# 3_-MCU_MAIN.net
KiCad netlist of a schematic drawn in Altium Designer
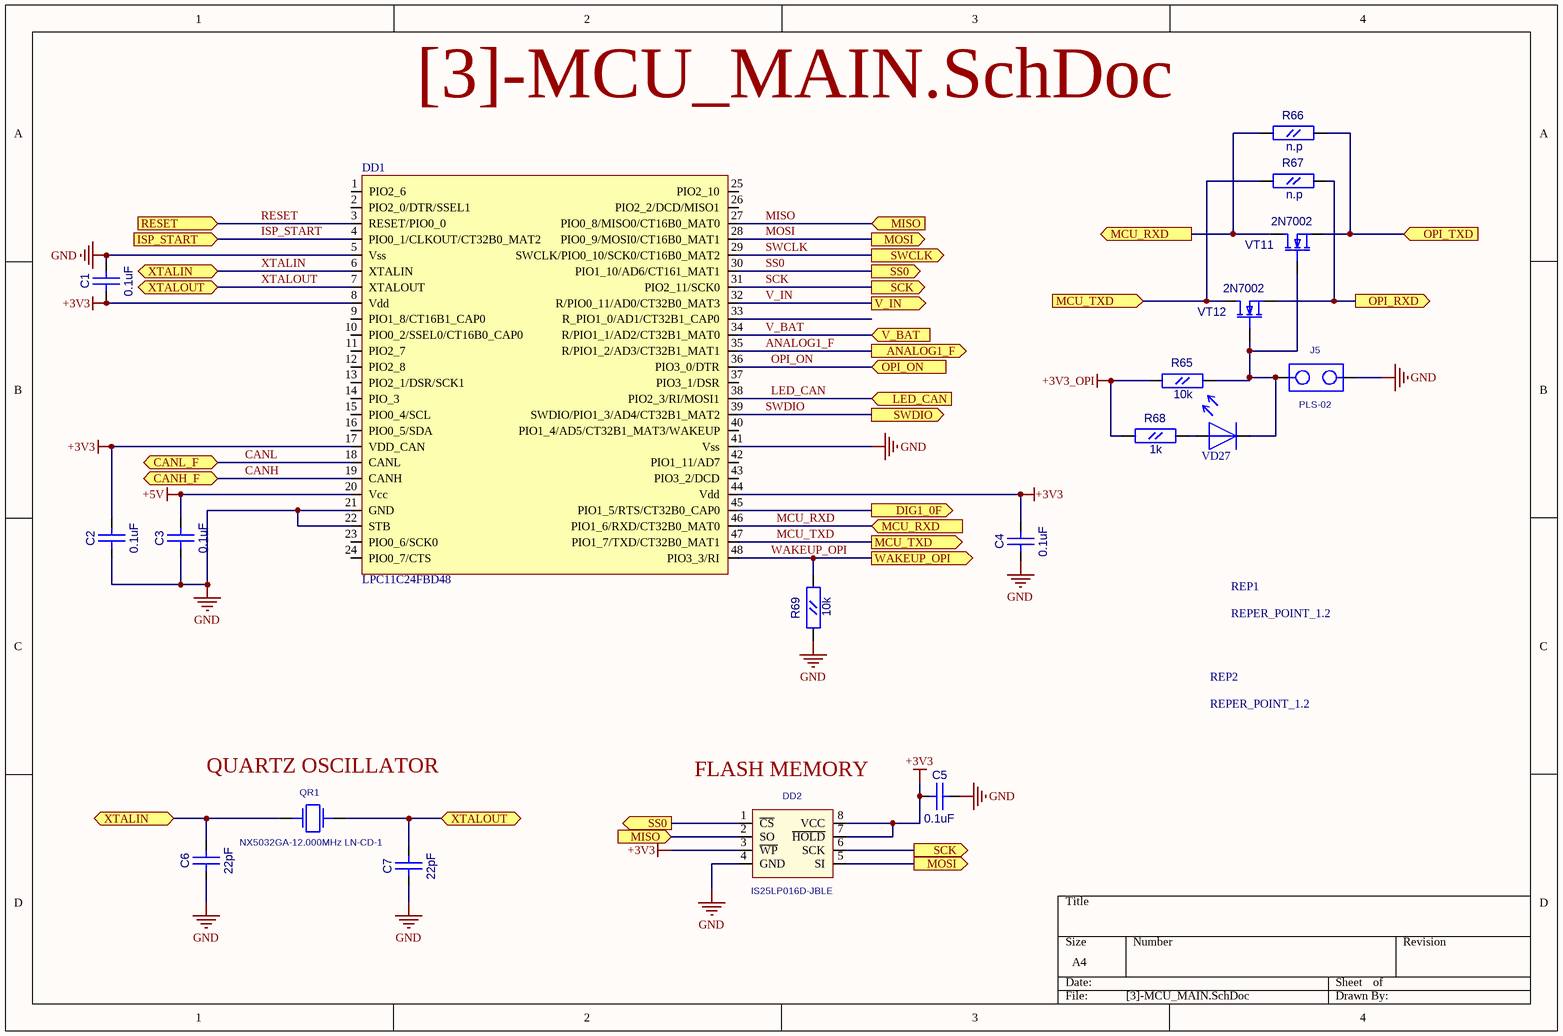
[diagram p0: [3]-MCU_MAIN.SchDoc]

(export (version "E")
  (design (tool "Eeschema 10.0.6"))
  (components
    (comp (ref "C1")
      (value "0.1uF")
      (footprint "CC0603")
      (description "CC0603")
      (libsource (lib "fizik_lib") (part "CC0603"))
    )
    (comp (ref "C2")
      (value "0.1uF")
      (footprint "CC0603")
      (description "CC0603")
      (libsource (lib "fizik_lib") (part "CC0603"))
    )
    (comp (ref "C3")
      (value "0.1uF")
      (footprint "CC0603")
      (description "CC0603")
      (libsource (lib "fizik_lib") (part "CC0603"))
    )
    (comp (ref "C4")
      (value "0.1uF")
      (footprint "CC0603")
      (description "CC0603")
      (libsource (lib "fizik_lib") (part "CC0603"))
    )
    (comp (ref "C5")
      (value "0.1uF")
      (footprint "CC0603")
      (description "CC0603")
      (libsource (lib "gprs_modem_2") (part "CC0603"))
    )
    (comp (ref "C6")
      (value "22pF")
      (footprint "CC0603")
      (description "CC0603")
      (libsource (lib "gprs_modem_2") (part "CC0603"))
    )
    (comp (ref "C7")
      (value "22pF")
      (footprint "CC0603")
      (description "CC0603")
      (libsource (lib "gprs_modem_2") (part "CC0603"))
    )
    (comp (ref "DD1")
      (value "LPC11C24FBD48")
      (footprint "LQFP48")
      (libsource (lib "fizik_lib") (part "LPC11C24FBD48"))
    )
    (comp (ref "DD2")
      (value "IS25LP016D-JBLE")
      (footprint "EIAJ_SO8")
      (description "S25FL016A0LMFI01")
      (libsource (lib "gprs_modem_2") (part "S25FL016A0LMFI01"))
    )
    (comp (ref "J5") (value "PLS-02") (footprint "PLS-02") (libsource (lib "fizik_lib") (part "PLS-02")))
    (comp (ref "QR1")
      (value "NX5032GA-12.000MHz LN-CD-1")
      (footprint "AC5032_2")
      (description "AC5032/2")
      (libsource (lib "gprs_modem_2") (part "AC5032_2"))
    )
    (comp (ref "R65")
      (value "10k")
      (footprint "RC0603")
      (description "RC0603")
      (libsource (lib "fizik_lib") (part "RC0603"))
    )
    (comp (ref "R66")
      (value "n.p")
      (footprint "RC0603")
      (description "RC0603")
      (libsource (lib "fizik_lib") (part "RC0603"))
    )
    (comp (ref "R67")
      (value "n.p")
      (footprint "RC0603")
      (description "RC0603")
      (libsource (lib "fizik_lib") (part "RC0603"))
    )
    (comp (ref "R68")
      (value "1k")
      (footprint "RC0603")
      (description "RC0603")
      (libsource (lib "fizik_lib") (part "RC0603"))
    )
    (comp (ref "R69")
      (value "10k")
      (footprint "RC0603")
      (description "RC0603")
      (libsource (lib "fizik_lib") (part "RC0603"))
    )
    (comp (ref "REP1")
      (value "REPER_POINT_1.2")
      (footprint "REPER1.2")
      (description "REPER1.2")
      (libsource (lib "fizik_lib") (part "REPER1.2"))
    )
    (comp (ref "REP2")
      (value "REPER_POINT_1.2")
      (footprint "REPER1.2")
      (description "REPER1.2")
      (libsource (lib "fizik_lib") (part "REPER1.2"))
    )
    (comp (ref "VD27")
      (value "LED_0805")
      (footprint "LED0805")
      (libsource (lib "fizik_lib") (part "LED_0805"))
    )
    (comp (ref "VT11")
      (value "2N7002")
      (footprint "SOT-23(123)")
      (description "N-Channel Enhancement Mode Vertical DMOS FET")
      (libsource (lib "fizik_lib") (part "2N7002"))
    )
    (comp (ref "VT12")
      (value "2N7002")
      (footprint "SOT-23(123)")
      (description "N-Channel Enhancement Mode Vertical DMOS FET")
      (libsource (lib "fizik_lib") (part "2N7002"))
    )
  )
  (nets
    (net (code "1") (name "+3V3") (class "Default")
      (node (ref "C1") (pin "1") (pinfunction "A_1") (pintype "passive"))
      (node (ref "C2") (pin "2") (pinfunction "B_2") (pintype "passive"))
      (node (ref "C4") (pin "2") (pinfunction "B_2") (pintype "passive"))
      (node (ref "C5") (pin "1") (pinfunction "A_1") (pintype "passive"))
      (node (ref "DD1") (pin "17") (pinfunction "VDD_CAN_17") (pintype "passive"))
      (node (ref "DD1") (pin "44") (pinfunction "Vdd_44") (pintype "passive"))
      (node (ref "DD1") (pin "8") (pinfunction "Vdd_8") (pintype "passive"))
      (node (ref "DD2") (pin "3") (pinfunction "~{WP}_3") (pintype "passive"))
      (node (ref "DD2") (pin "7") (pinfunction "~{HOLD}_7") (pintype "passive"))
      (node (ref "DD2") (pin "8") (pinfunction "VCC_8") (pintype "passive"))
    )
    (net (code "2") (name "+3V3_OPI") (class "Default")
      (node (ref "R65") (pin "1") (pinfunction "A_1") (pintype "passive"))
      (node (ref "R68") (pin "1") (pinfunction "A_1") (pintype "passive"))
    )
    (net (code "3") (name "+5V") (class "Default")
      (node (ref "C3") (pin "2") (pinfunction "B_2") (pintype "passive"))
      (node (ref "DD1") (pin "20") (pinfunction "Vcc_20") (pintype "passive"))
    )
    (net (code "4") (name "/ANALOG1_F") (class "Default")
      (node (ref "DD1") (pin "35") (pinfunction "R/PIO1_2/AD3/CT32B1_MAT1_35") (pintype "passive"))
    )
    (net (code "5") (name "/CANH") (class "Default")
      (node (ref "DD1") (pin "19") (pinfunction "CANH_19") (pintype "passive"))
    )
    (net (code "6") (name "/CANL") (class "Default")
      (node (ref "DD1") (pin "18") (pinfunction "CANL_18") (pintype "passive"))
    )
    (net (code "7") (name "/DIG1_0F") (class "Default")
      (node (ref "DD1") (pin "45") (pinfunction "PIO1_5/RTS/CT32B0_CAP0_45") (pintype "passive"))
    )
    (net (code "8") (name "/ISP_START") (class "Default")
      (node (ref "DD1") (pin "4") (pinfunction "PIO0_1/CLKOUT/CT32B0_MAT2_4") (pintype "passive"))
    )
    (net (code "9") (name "/LED_CAN") (class "Default")
      (node (ref "DD1") (pin "38") (pinfunction "PIO2_3/RI/MOSI1_38") (pintype "passive"))
    )
    (net (code "10") (name "/MCU_RXD") (class "Default")
      (node (ref "DD1") (pin "46") (pinfunction "PIO1_6/RXD/CT32B0_MAT0_46") (pintype "passive"))
      (node (ref "R66") (pin "1") (pinfunction "A_1") (pintype "passive"))
      (node (ref "VT11") (pin "3") (pinfunction "D_3") (pintype "passive"))
    )
    (net (code "11") (name "/MCU_TXD") (class "Default")
      (node (ref "DD1") (pin "47") (pinfunction "PIO1_7/TXD/CT32B0_MAT1_47") (pintype "passive"))
      (node (ref "R67") (pin "1") (pinfunction "A_1") (pintype "passive"))
      (node (ref "VT12") (pin "3") (pinfunction "D_3") (pintype "passive"))
    )
    (net (code "12") (name "/MISO") (class "Default")
      (node (ref "DD1") (pin "27") (pinfunction "PIO0_8/MISO0/CT16B0_MAT0_27") (pintype "passive"))
      (node (ref "DD2") (pin "2") (pinfunction "SO_2") (pintype "passive"))
    )
    (net (code "13") (name "/MOSI") (class "Default")
      (node (ref "DD1") (pin "28") (pinfunction "PIO0_9/MOSI0/CT16B0_MAT1_28") (pintype "passive"))
      (node (ref "DD2") (pin "5") (pinfunction "SI_5") (pintype "passive"))
    )
    (net (code "14") (name "/OPI_ON") (class "Default")
      (node (ref "DD1") (pin "36") (pinfunction "PIO3_0/DTR_36") (pintype "passive"))
    )
    (net (code "15") (name "/OPI_RXD") (class "Default")
      (node (ref "R67") (pin "2") (pinfunction "B_2") (pintype "passive"))
      (node (ref "VT12") (pin "2") (pinfunction "S_2") (pintype "passive"))
    )
    (net (code "16") (name "/OPI_TXD") (class "Default")
      (node (ref "R66") (pin "2") (pinfunction "B_2") (pintype "passive"))
      (node (ref "VT11") (pin "2") (pinfunction "S_2") (pintype "passive"))
    )
    (net (code "17") (name "/RESET") (class "Default")
      (node (ref "DD1") (pin "3") (pinfunction "RESET/PIO0_0_3") (pintype "passive"))
    )
    (net (code "18") (name "/SCK") (class "Default")
      (node (ref "DD1") (pin "31") (pinfunction "PIO2_11/SCK0_31") (pintype "passive"))
      (node (ref "DD2") (pin "6") (pinfunction "SCK_6") (pintype "passive"))
    )
    (net (code "19") (name "/SS0") (class "Default")
      (node (ref "DD1") (pin "30") (pinfunction "PIO1_10/AD6/CT161_MAT1_30") (pintype "passive"))
      (node (ref "DD2") (pin "1") (pinfunction "~{CS}_1") (pintype "passive"))
    )
    (net (code "20") (name "/SWCLK") (class "Default")
      (node (ref "DD1") (pin "29") (pinfunction "SWCLK/PIO0_10/SCK0/CT16B0_MAT2_29") (pintype "passive"))
    )
    (net (code "21") (name "/SWDIO") (class "Default")
      (node (ref "DD1") (pin "39") (pinfunction "SWDIO/PIO1_3/AD4/CT32B1_MAT2_39") (pintype "passive"))
    )
    (net (code "22") (name "/V_BAT") (class "Default")
      (node (ref "DD1") (pin "34") (pinfunction "R/PIO1_1/AD2/CT32B1_MAT0_34") (pintype "passive"))
    )
    (net (code "23") (name "/V_IN") (class "Default")
      (node (ref "DD1") (pin "32") (pinfunction "R/PIO0_11/AD0/CT32B0_MAT3_32") (pintype "passive"))
    )
    (net (code "24") (name "/WAKEUP_OPI") (class "Default")
      (node (ref "DD1") (pin "48") (pinfunction "PIO3_3/RI_48") (pintype "passive"))
      (node (ref "R69") (pin "2") (pinfunction "B_2") (pintype "passive"))
    )
    (net (code "25") (name "/XTALIN") (class "Default")
      (node (ref "C6") (pin "2") (pinfunction "B_2") (pintype "passive"))
      (node (ref "DD1") (pin "6") (pinfunction "XTALIN_6") (pintype "passive"))
      (node (ref "QR1") (pin "1") (pintype "passive"))
    )
    (net (code "26") (name "/XTALOUT") (class "Default")
      (node (ref "C7") (pin "2") (pinfunction "B_2") (pintype "passive"))
      (node (ref "DD1") (pin "7") (pinfunction "XTALOUT_7") (pintype "passive"))
      (node (ref "QR1") (pin "2") (pintype "passive"))
    )
    (net (code "27") (name "GND") (class "Default")
      (node (ref "C1") (pin "2") (pinfunction "B_2") (pintype "passive"))
      (node (ref "C2") (pin "1") (pinfunction "A_1") (pintype "passive"))
      (node (ref "C3") (pin "1") (pinfunction "A_1") (pintype "passive"))
      (node (ref "C4") (pin "1") (pinfunction "A_1") (pintype "passive"))
      (node (ref "C5") (pin "2") (pinfunction "B_2") (pintype "passive"))
      (node (ref "C6") (pin "1") (pinfunction "A_1") (pintype "passive"))
      (node (ref "C7") (pin "1") (pinfunction "A_1") (pintype "passive"))
      (node (ref "DD1") (pin "21") (pinfunction "GND_21") (pintype "passive"))
      (node (ref "DD1") (pin "22") (pinfunction "STB_22") (pintype "passive"))
      (node (ref "DD1") (pin "41") (pinfunction "Vss_41") (pintype "passive"))
      (node (ref "DD1") (pin "5") (pinfunction "Vss_5") (pintype "passive"))
      (node (ref "DD2") (pin "4") (pinfunction "GND_4") (pintype "passive"))
      (node (ref "J5") (pin "2") (pintype "passive"))
      (node (ref "R69") (pin "1") (pinfunction "A_1") (pintype "passive"))
    )
    (net (code "28") (name "Net-(R65-B)") (class "Default")
      (node (ref "J5") (pin "1") (pintype "passive"))
      (node (ref "R65") (pin "2") (pinfunction "B_2") (pintype "passive"))
      (node (ref "VD27") (pin "2") (pintype "passive"))
      (node (ref "VT11") (pin "1") (pinfunction "G_1") (pintype "passive"))
      (node (ref "VT12") (pin "1") (pinfunction "G_1") (pintype "passive"))
    )
    (net (code "29") (name "Net-(R68-B)") (class "Default")
      (node (ref "R68") (pin "2") (pinfunction "B_2") (pintype "passive"))
      (node (ref "VD27") (pin "1") (pintype "passive"))
    )
    (net (code "30") (name "unconnected-(DD1-PIO0_2{slash}SSEL0{slash}CT16B0_CAP0-Pad10)") (class "Default")
      (node (ref "DD1") (pin "10") (pinfunction "PIO0_2/SSEL0/CT16B0_CAP0_10") (pintype "passive"))
    )
    (net (code "31") (name "unconnected-(DD1-PIO0_4{slash}SCL-Pad15)") (class "Default")
      (node (ref "DD1") (pin "15") (pinfunction "PIO0_4/SCL_15") (pintype "passive"))
    )
    (net (code "32") (name "unconnected-(DD1-PIO0_5{slash}SDA-Pad16)") (class "Default")
      (node (ref "DD1") (pin "16") (pinfunction "PIO0_5/SDA_16") (pintype "passive"))
    )
    (net (code "33") (name "unconnected-(DD1-PIO0_6{slash}SCK0-Pad23)") (class "Default")
      (node (ref "DD1") (pin "23") (pinfunction "PIO0_6/SCK0_23") (pintype "passive"))
    )
    (net (code "34") (name "unconnected-(DD1-PIO0_7{slash}CTS-Pad24)") (class "Default")
      (node (ref "DD1") (pin "24") (pinfunction "PIO0_7/CTS_24") (pintype "passive"))
    )
    (net (code "35") (name "unconnected-(DD1-PIO1_4{slash}AD5{slash}CT32B1_MAT3{slash}WAKEUP-Pad40)") (class "Default")
      (node (ref "DD1") (pin "40") (pinfunction "PIO1_4/AD5/CT32B1_MAT3/WAKEUP_40") (pintype "passive"))
    )
    (net (code "36") (name "unconnected-(DD1-PIO1_8{slash}CT16B1_CAP0-Pad9)") (class "Default")
      (node (ref "DD1") (pin "9") (pinfunction "PIO1_8/CT16B1_CAP0_9") (pintype "passive"))
    )
    (net (code "37") (name "unconnected-(DD1-PIO1_11{slash}AD7-Pad42)") (class "Default")
      (node (ref "DD1") (pin "42") (pinfunction "PIO1_11/AD7_42") (pintype "passive"))
    )
    (net (code "38") (name "unconnected-(DD1-PIO2_0{slash}DTR{slash}SSEL1-Pad2)") (class "Default")
      (node (ref "DD1") (pin "2") (pinfunction "PIO2_0/DTR/SSEL1_2") (pintype "passive"))
    )
    (net (code "39") (name "unconnected-(DD1-PIO2_1{slash}DSR{slash}SCK1-Pad13)") (class "Default")
      (node (ref "DD1") (pin "13") (pinfunction "PIO2_1/DSR/SCK1_13") (pintype "passive"))
    )
    (net (code "40") (name "unconnected-(DD1-PIO2_2{slash}DCD{slash}MISO1-Pad26)") (class "Default")
      (node (ref "DD1") (pin "26") (pinfunction "PIO2_2/DCD/MISO1_26") (pintype "passive"))
    )
    (net (code "41") (name "unconnected-(DD1-PIO2_6-Pad1)") (class "Default")
      (node (ref "DD1") (pin "1") (pinfunction "PIO2_6_1") (pintype "passive"))
    )
    (net (code "42") (name "unconnected-(DD1-PIO2_7-Pad11)") (class "Default")
      (node (ref "DD1") (pin "11") (pinfunction "PIO2_7_11") (pintype "passive"))
    )
    (net (code "43") (name "unconnected-(DD1-PIO2_8-Pad12)") (class "Default")
      (node (ref "DD1") (pin "12") (pinfunction "PIO2_8_12") (pintype "passive"))
    )
    (net (code "44") (name "unconnected-(DD1-PIO2_10-Pad25)") (class "Default")
      (node (ref "DD1") (pin "25") (pinfunction "PIO2_10_25") (pintype "passive"))
    )
    (net (code "45") (name "unconnected-(DD1-PIO3_1{slash}DSR-Pad37)") (class "Default")
      (node (ref "DD1") (pin "37") (pinfunction "PIO3_1/DSR_37") (pintype "passive"))
    )
    (net (code "46") (name "unconnected-(DD1-PIO3_2{slash}DCD-Pad43)") (class "Default")
      (node (ref "DD1") (pin "43") (pinfunction "PIO3_2/DCD_43") (pintype "passive"))
    )
    (net (code "47") (name "unconnected-(DD1-PIO_3-Pad14)") (class "Default")
      (node (ref "DD1") (pin "14") (pinfunction "PIO_3_14") (pintype "passive"))
    )
    (net (code "48") (name "unconnected-(DD1-R_PIO1_0{slash}AD1{slash}CT32B1_CAP0-Pad33)") (class "Default")
      (node (ref "DD1") (pin "33") (pinfunction "R_PIO1_0/AD1/CT32B1_CAP0_33") (pintype "passive"))
    )
    (net (code "49") (name "unconnected-(REP1-Pad1)") (class "Default")
      (node (ref "REP1") (pin "1") (pintype "passive"))
    )
    (net (code "50") (name "unconnected-(REP2-Pad1)") (class "Default")
      (node (ref "REP2") (pin "1") (pintype "passive"))
    )
  )
)
